# dab_mainboard.net
KiCad netlist of a schematic drawn in EAGLE
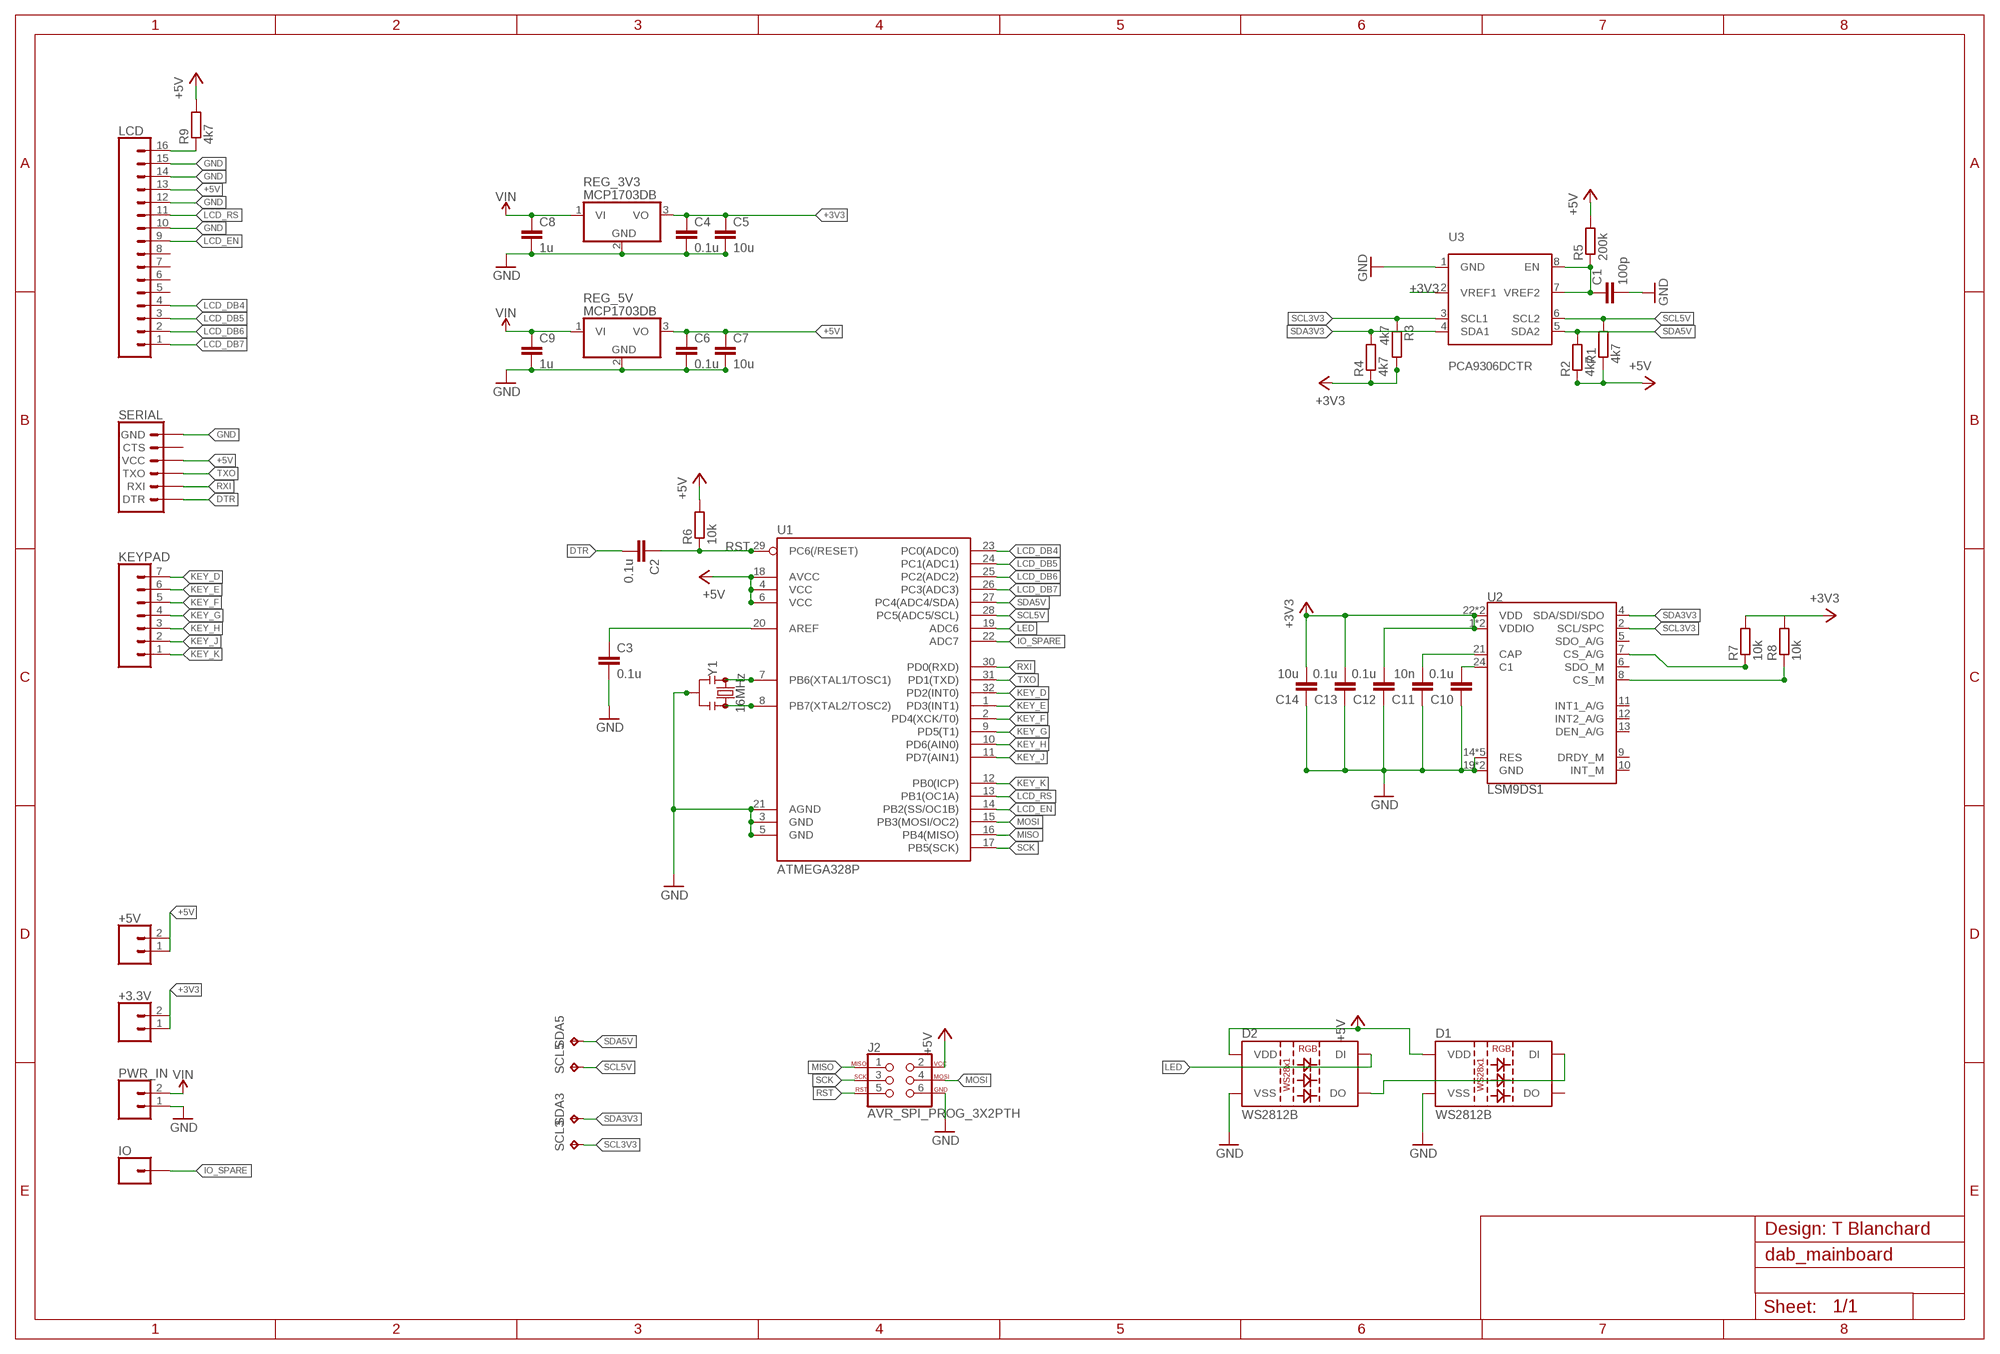
[diagram p0: schematic, sheet 1]

(export (version "E")
  (design (tool "Eeschema 10.0.6"))
  (components
    (comp (ref "+3.3V")
      (value "CONN_02")
      (footprint "eagle-import:1X02")
      (libsource (lib "eagle-import") (part "CONN_02"))
    )
    (comp (ref "+5V")
      (value "CONN_02")
      (footprint "eagle-import:1X02")
      (libsource (lib "eagle-import") (part "CONN_02"))
    )
    (comp (ref "C1")
      (value "100p")
      (footprint "eagle-import:C0603")
      (libsource (lib "eagle-import") (part "C-EUC0603"))
    )
    (comp (ref "C2")
      (value "0.1u")
      (footprint "eagle-import:C0603")
      (libsource (lib "eagle-import") (part "C-EUC0603"))
    )
    (comp (ref "C3")
      (value "0.1u")
      (footprint "eagle-import:C0603")
      (libsource (lib "eagle-import") (part "C-EUC0603"))
    )
    (comp (ref "C4")
      (value "0.1u")
      (footprint "eagle-import:C0603")
      (libsource (lib "eagle-import") (part "C-EUC0603"))
    )
    (comp (ref "C5")
      (value "10u")
      (footprint "eagle-import:C0603")
      (libsource (lib "eagle-import") (part "C-EUC0603"))
    )
    (comp (ref "C6")
      (value "0.1u")
      (footprint "eagle-import:C0603")
      (libsource (lib "eagle-import") (part "C-EUC0603"))
    )
    (comp (ref "C7")
      (value "10u")
      (footprint "eagle-import:C0603")
      (libsource (lib "eagle-import") (part "C-EUC0603"))
    )
    (comp (ref "C8")
      (value "1u")
      (footprint "eagle-import:C0603")
      (libsource (lib "eagle-import") (part "C-EUC0603"))
    )
    (comp (ref "C9")
      (value "1u")
      (footprint "eagle-import:C0603")
      (libsource (lib "eagle-import") (part "C-EUC0603"))
    )
    (comp (ref "C10")
      (value "0.1u")
      (footprint "eagle-import:C0603")
      (libsource (lib "eagle-import") (part "C-EUC0603"))
    )
    (comp (ref "C11")
      (value "10n")
      (footprint "eagle-import:C0603")
      (libsource (lib "eagle-import") (part "C-EUC0603"))
    )
    (comp (ref "C12")
      (value "0.1u")
      (footprint "eagle-import:C0603")
      (libsource (lib "eagle-import") (part "C-EUC0603"))
    )
    (comp (ref "C13")
      (value "0.1u")
      (footprint "eagle-import:C0603")
      (libsource (lib "eagle-import") (part "C-EUC0603"))
    )
    (comp (ref "C14")
      (value "10u")
      (footprint "eagle-import:C0603")
      (libsource (lib "eagle-import") (part "C-EUC0603"))
    )
    (comp (ref "D1")
      (value "WS2812B")
      (footprint "eagle-import:WS2812B")
      (libsource (lib "eagle-import") (part "WS2812B"))
    )
    (comp (ref "D2")
      (value "WS2812B")
      (footprint "eagle-import:WS2812B")
      (libsource (lib "eagle-import") (part "WS2812B"))
    )
    (comp (ref "IO")
      (value "CONN_01")
      (footprint "eagle-import:1X01")
      (libsource (lib "eagle-import") (part "CONN_01"))
    )
    (comp (ref "J2")
      (value "AVR_SPI_PROG_3X2PTH")
      (footprint "eagle-import:2X3")
      (libsource (lib "eagle-import") (part "AVR_SPI_PROG_3X2PTH"))
    )
    (comp (ref "KEYPAD")
      (value "CONN_07")
      (footprint "eagle-import:1X07")
      (libsource (lib "eagle-import") (part "CONN_07"))
    )
    (comp (ref "LCD")
      (value "CONN_16")
      (footprint "eagle-import:1X16")
      (libsource (lib "eagle-import") (part "CONN_16"))
    )
    (comp (ref "PWR_IN")
      (value "CONN_02")
      (footprint "eagle-import:1X02")
      (libsource (lib "eagle-import") (part "CONN_02"))
    )
    (comp (ref "R1")
      (value "4k7")
      (footprint "eagle-import:R0603")
      (libsource (lib "eagle-import") (part "R-EU_R0603"))
    )
    (comp (ref "R2")
      (value "4k7")
      (footprint "eagle-import:R0603")
      (libsource (lib "eagle-import") (part "R-EU_R0603"))
    )
    (comp (ref "R3")
      (value "4k7")
      (footprint "eagle-import:R0603")
      (libsource (lib "eagle-import") (part "R-EU_R0603"))
    )
    (comp (ref "R4")
      (value "4k7")
      (footprint "eagle-import:R0603")
      (libsource (lib "eagle-import") (part "R-EU_R0603"))
    )
    (comp (ref "R5")
      (value "200k")
      (footprint "eagle-import:R0603")
      (libsource (lib "eagle-import") (part "R-EU_R0603"))
    )
    (comp (ref "R6")
      (value "10k")
      (footprint "eagle-import:R0603")
      (libsource (lib "eagle-import") (part "R-EU_R0603"))
    )
    (comp (ref "R7")
      (value "10k")
      (footprint "eagle-import:R0603")
      (libsource (lib "eagle-import") (part "R-EU_R0603"))
    )
    (comp (ref "R8")
      (value "10k")
      (footprint "eagle-import:R0603")
      (libsource (lib "eagle-import") (part "R-EU_R0603"))
    )
    (comp (ref "R9")
      (value "4k7")
      (footprint "eagle-import:R0603")
      (libsource (lib "eagle-import") (part "R-EU_R0603"))
    )
    (comp (ref "REG_3V3")
      (value "MCP1703DB")
      (footprint "eagle-import:SOT223")
      (libsource (lib "eagle-import") (part "MCP1703DB"))
    )
    (comp (ref "REG_5V")
      (value "MCP1703DB")
      (footprint "eagle-import:SOT223")
      (libsource (lib "eagle-import") (part "MCP1703DB"))
    )
    (comp (ref "SCL3")
      (value "TPTP08R")
      (footprint "eagle-import:TP08R")
      (libsource (lib "eagle-import") (part "TPTP08R"))
    )
    (comp (ref "SCL5")
      (value "TPTP08R")
      (footprint "eagle-import:TP08R")
      (libsource (lib "eagle-import") (part "TPTP08R"))
    )
    (comp (ref "SDA3")
      (value "TPTP08R")
      (footprint "eagle-import:TP08R")
      (libsource (lib "eagle-import") (part "TPTP08R"))
    )
    (comp (ref "SDA5")
      (value "TPTP08R")
      (footprint "eagle-import:TP08R")
      (libsource (lib "eagle-import") (part "TPTP08R"))
    )
    (comp (ref "SERIAL")
      (value "6_PIN_SERIAL_TARGETSILK")
      (footprint "eagle-import:6_PIN_SERIAL_TARGET_SIDE_W_SILK")
      (libsource (lib "eagle-import") (part "6_PIN_SERIAL_TARGETSILK"))
    )
    (comp (ref "U1")
      (value "ATMEGA328P")
      (footprint "eagle-import:TQFP32-08")
      (libsource (lib "eagle-import") (part "ATMEGA328P_TQFP"))
    )
    (comp (ref "U2")
      (value "LSM9DS1")
      (footprint "eagle-import:LGA-24-3.5X3")
      (libsource (lib "eagle-import") (part "LSM9DS1"))
    )
    (comp (ref "U3")
      (value "PCA9306DCTR")
      (footprint "eagle-import:SM8")
      (libsource (lib "eagle-import") (part "PCA9306DCTR"))
    )
    (comp (ref "Y1")
      (value "16MHz")
      (footprint "eagle-import:RESONATOR-SMD-3.2X1.3")
      (libsource (lib "eagle-import") (part "RESONATOR-16MHZSMD_3.2X1.3"))
    )
  )
  (nets
    (net (code "1") (name "+3V3") (class "Default")
      (node (ref "+3.3V") (pin "1") (pinfunction "1_1") (pintype "passive"))
      (node (ref "+3.3V") (pin "2") (pinfunction "2_2") (pintype "passive"))
      (node (ref "C12") (pin "2") (pinfunction "2_2") (pintype "passive"))
      (node (ref "C13") (pin "2") (pinfunction "2_2") (pintype "passive"))
      (node (ref "C14") (pin "2") (pinfunction "2_2") (pintype "passive"))
      (node (ref "C4") (pin "1") (pinfunction "1_1") (pintype "passive"))
      (node (ref "C5") (pin "1") (pinfunction "1_1") (pintype "passive"))
      (node (ref "R3") (pin "2") (pinfunction "2_2") (pintype "passive"))
      (node (ref "R4") (pin "1") (pinfunction "1_1") (pintype "passive"))
      (node (ref "R7") (pin "2") (pinfunction "2_2") (pintype "passive"))
      (node (ref "R8") (pin "2") (pinfunction "2_2") (pintype "passive"))
      (node (ref "REG_3V3") (pin "3") (pinfunction "VO_3") (pintype "passive"))
      (node (ref "U2") (pin "1") (pinfunction "VDDIO_1") (pintype "bidirectional"))
      (node (ref "U2") (pin "22") (pinfunction "VDD_22") (pintype "bidirectional"))
      (node (ref "U2") (pin "23") (pinfunction "VDD_23") (pintype "bidirectional"))
      (node (ref "U2") (pin "3") (pinfunction "VDDIO_3") (pintype "bidirectional"))
      (node (ref "U3") (pin "2") (pinfunction "VREF1_2") (pintype "power_in"))
    )
    (net (code "2") (name "+5V") (class "Default")
      (node (ref "+5V") (pin "1") (pinfunction "1_1") (pintype "passive"))
      (node (ref "+5V") (pin "2") (pinfunction "2_2") (pintype "passive"))
      (node (ref "C6") (pin "1") (pinfunction "1_1") (pintype "passive"))
      (node (ref "C7") (pin "1") (pinfunction "1_1") (pintype "passive"))
      (node (ref "D1") (pin "1") (pinfunction "VDD_1") (pintype "bidirectional"))
      (node (ref "D2") (pin "1") (pinfunction "VDD_1") (pintype "bidirectional"))
      (node (ref "J2") (pin "2") (pinfunction "2_2") (pintype "passive"))
      (node (ref "LCD") (pin "13") (pinfunction "13_13") (pintype "passive"))
      (node (ref "R1") (pin "1") (pinfunction "1_1") (pintype "passive"))
      (node (ref "R2") (pin "1") (pinfunction "1_1") (pintype "passive"))
      (node (ref "R5") (pin "2") (pinfunction "2_2") (pintype "passive"))
      (node (ref "R6") (pin "2") (pinfunction "2_2") (pintype "passive"))
      (node (ref "R9") (pin "2") (pinfunction "2_2") (pintype "passive"))
      (node (ref "REG_5V") (pin "3") (pinfunction "VO_3") (pintype "passive"))
      (node (ref "SERIAL") (pin "P$4") (pinfunction "VCC_P$4") (pintype "passive"))
      (node (ref "U1") (pin "18") (pinfunction "AVCC_18") (pintype "bidirectional"))
      (node (ref "U1") (pin "4") (pinfunction "VCC_4") (pintype "bidirectional"))
      (node (ref "U1") (pin "6") (pinfunction "VCC_6") (pintype "bidirectional"))
    )
    (net (code "3") (name "DTR") (class "Default")
      (node (ref "C2") (pin "2") (pinfunction "2_2") (pintype "passive"))
      (node (ref "SERIAL") (pin "P$1") (pinfunction "DTR_P$1") (pintype "passive"))
    )
    (net (code "4") (name "GND") (class "Default")
      (node (ref "C1") (pin "2") (pinfunction "2_2") (pintype "passive"))
      (node (ref "C10") (pin "1") (pinfunction "1_1") (pintype "passive"))
      (node (ref "C11") (pin "1") (pinfunction "1_1") (pintype "passive"))
      (node (ref "C12") (pin "1") (pinfunction "1_1") (pintype "passive"))
      (node (ref "C13") (pin "1") (pinfunction "1_1") (pintype "passive"))
      (node (ref "C14") (pin "1") (pinfunction "1_1") (pintype "passive"))
      (node (ref "C3") (pin "2") (pinfunction "2_2") (pintype "passive"))
      (node (ref "C4") (pin "2") (pinfunction "2_2") (pintype "passive"))
      (node (ref "C5") (pin "2") (pinfunction "2_2") (pintype "passive"))
      (node (ref "C6") (pin "2") (pinfunction "2_2") (pintype "passive"))
      (node (ref "C7") (pin "2") (pinfunction "2_2") (pintype "passive"))
      (node (ref "C8") (pin "2") (pinfunction "2_2") (pintype "passive"))
      (node (ref "C9") (pin "2") (pinfunction "2_2") (pintype "passive"))
      (node (ref "D1") (pin "3") (pinfunction "VSS_3") (pintype "bidirectional"))
      (node (ref "D2") (pin "3") (pinfunction "VSS_3") (pintype "bidirectional"))
      (node (ref "J2") (pin "6") (pinfunction "6_6") (pintype "passive"))
      (node (ref "LCD") (pin "10") (pinfunction "10_10") (pintype "passive"))
      (node (ref "LCD") (pin "12") (pinfunction "12_12") (pintype "passive"))
      (node (ref "LCD") (pin "14") (pinfunction "14_14") (pintype "passive"))
      (node (ref "LCD") (pin "15") (pinfunction "15_15") (pintype "passive"))
      (node (ref "PWR_IN") (pin "1") (pinfunction "1_1") (pintype "passive"))
      (node (ref "REG_3V3") (pin "2") (pinfunction "GND_2") (pintype "passive"))
      (node (ref "REG_5V") (pin "2") (pinfunction "GND_2") (pintype "passive"))
      (node (ref "SERIAL") (pin "P$6") (pinfunction "GND_P$6") (pintype "passive"))
      (node (ref "U1") (pin "21") (pinfunction "AGND_21") (pintype "bidirectional"))
      (node (ref "U1") (pin "3") (pinfunction "GND_3") (pintype "bidirectional"))
      (node (ref "U1") (pin "5") (pinfunction "GND_5") (pintype "bidirectional"))
      (node (ref "U2") (pin "14") (pinfunction "RES_14") (pintype "bidirectional"))
      (node (ref "U2") (pin "15") (pinfunction "RES_15") (pintype "bidirectional"))
      (node (ref "U2") (pin "16") (pinfunction "RES_16") (pintype "bidirectional"))
      (node (ref "U2") (pin "17") (pinfunction "RES_17") (pintype "bidirectional"))
      (node (ref "U2") (pin "18") (pinfunction "RES_18") (pintype "bidirectional"))
      (node (ref "U2") (pin "19") (pinfunction "GND_19") (pintype "bidirectional"))
      (node (ref "U2") (pin "20") (pinfunction "GND_20") (pintype "bidirectional"))
      (node (ref "U3") (pin "1") (pinfunction "GND_1") (pintype "power_in"))
      (node (ref "Y1") (pin "2") (pinfunction "2_2") (pintype "passive"))
    )
    (net (code "5") (name "IO_SPARE") (class "Default")
      (node (ref "IO") (pin "1") (pinfunction "1_1") (pintype "passive"))
      (node (ref "U1") (pin "22") (pinfunction "ADC7_22") (pintype "bidirectional"))
    )
    (net (code "6") (name "KEY_D") (class "Default")
      (node (ref "KEYPAD") (pin "7") (pinfunction "7_7") (pintype "passive"))
      (node (ref "U1") (pin "32") (pinfunction "PD2(INT0)_32") (pintype "bidirectional"))
    )
    (net (code "7") (name "KEY_E") (class "Default")
      (node (ref "KEYPAD") (pin "6") (pinfunction "6_6") (pintype "passive"))
      (node (ref "U1") (pin "1") (pinfunction "PD3(INT1)_1") (pintype "bidirectional"))
    )
    (net (code "8") (name "KEY_F") (class "Default")
      (node (ref "KEYPAD") (pin "5") (pinfunction "5_5") (pintype "passive"))
      (node (ref "U1") (pin "2") (pinfunction "PD4(XCK/T0)_2") (pintype "bidirectional"))
    )
    (net (code "9") (name "KEY_G") (class "Default")
      (node (ref "KEYPAD") (pin "4") (pinfunction "4_4") (pintype "passive"))
      (node (ref "U1") (pin "9") (pinfunction "PD5(T1)_9") (pintype "bidirectional"))
    )
    (net (code "10") (name "KEY_H") (class "Default")
      (node (ref "KEYPAD") (pin "3") (pinfunction "3_3") (pintype "passive"))
      (node (ref "U1") (pin "10") (pinfunction "PD6(AIN0)_10") (pintype "bidirectional"))
    )
    (net (code "11") (name "KEY_J") (class "Default")
      (node (ref "KEYPAD") (pin "2") (pinfunction "2_2") (pintype "passive"))
      (node (ref "U1") (pin "11") (pinfunction "PD7(AIN1)_11") (pintype "bidirectional"))
    )
    (net (code "12") (name "KEY_K") (class "Default")
      (node (ref "KEYPAD") (pin "1") (pinfunction "1_1") (pintype "passive"))
      (node (ref "U1") (pin "12") (pinfunction "PB0(ICP)_12") (pintype "bidirectional"))
    )
    (net (code "13") (name "LCD_DB4") (class "Default")
      (node (ref "LCD") (pin "4") (pinfunction "4_4") (pintype "passive"))
      (node (ref "U1") (pin "23") (pinfunction "PC0(ADC0)_23") (pintype "bidirectional"))
    )
    (net (code "14") (name "LCD_DB5") (class "Default")
      (node (ref "LCD") (pin "3") (pinfunction "3_3") (pintype "passive"))
      (node (ref "U1") (pin "24") (pinfunction "PC1(ADC1)_24") (pintype "bidirectional"))
    )
    (net (code "15") (name "LCD_DB6") (class "Default")
      (node (ref "LCD") (pin "2") (pinfunction "2_2") (pintype "passive"))
      (node (ref "U1") (pin "25") (pinfunction "PC2(ADC2)_25") (pintype "bidirectional"))
    )
    (net (code "16") (name "LCD_DB7") (class "Default")
      (node (ref "LCD") (pin "1") (pinfunction "1_1") (pintype "passive"))
      (node (ref "U1") (pin "26") (pinfunction "PC3(ADC3)_26") (pintype "bidirectional"))
    )
    (net (code "17") (name "LCD_EN") (class "Default")
      (node (ref "LCD") (pin "9") (pinfunction "9_9") (pintype "passive"))
      (node (ref "U1") (pin "14") (pinfunction "PB2(SS/OC1B)_14") (pintype "bidirectional"))
    )
    (net (code "18") (name "LCD_RS") (class "Default")
      (node (ref "LCD") (pin "11") (pinfunction "11_11") (pintype "passive"))
      (node (ref "U1") (pin "13") (pinfunction "PB1(OC1A)_13") (pintype "bidirectional"))
    )
    (net (code "19") (name "LED") (class "Default")
      (node (ref "D2") (pin "4") (pinfunction "DI_4") (pintype "bidirectional"))
      (node (ref "U1") (pin "19") (pinfunction "ADC6_19") (pintype "bidirectional"))
    )
    (net (code "20") (name "MISO") (class "Default")
      (node (ref "J2") (pin "1") (pinfunction "1_1") (pintype "passive"))
      (node (ref "U1") (pin "16") (pinfunction "PB4(MISO)_16") (pintype "bidirectional"))
    )
    (net (code "21") (name "MOSI") (class "Default")
      (node (ref "J2") (pin "4") (pinfunction "4_4") (pintype "passive"))
      (node (ref "U1") (pin "15") (pinfunction "PB3(MOSI/OC2)_15") (pintype "bidirectional"))
    )
    (net (code "22") (name "Net-(D1-DI)") (class "Default")
      (node (ref "D1") (pin "4") (pinfunction "DI_4") (pintype "bidirectional"))
      (node (ref "D2") (pin "2") (pinfunction "DO_2") (pintype "bidirectional"))
    )
    (net (code "23") (name "Net-(LCD-Pad16)") (class "Default")
      (node (ref "LCD") (pin "16") (pinfunction "16_16") (pintype "passive"))
      (node (ref "R9") (pin "1") (pinfunction "1_1") (pintype "passive"))
    )
    (net (code "24") (name "Net-(U1-AREF)") (class "Default")
      (node (ref "C3") (pin "1") (pinfunction "1_1") (pintype "passive"))
      (node (ref "U1") (pin "20") (pinfunction "AREF_20") (pintype "bidirectional"))
    )
    (net (code "25") (name "Net-(U1-PB6(XTAL1{slash}TOSC1))") (class "Default")
      (node (ref "U1") (pin "7") (pinfunction "PB6(XTAL1/TOSC1)_7") (pintype "bidirectional"))
      (node (ref "Y1") (pin "1") (pinfunction "1_1") (pintype "passive"))
    )
    (net (code "26") (name "Net-(U1-PB7(XTAL2{slash}TOSC2))") (class "Default")
      (node (ref "U1") (pin "8") (pinfunction "PB7(XTAL2/TOSC2)_8") (pintype "bidirectional"))
      (node (ref "Y1") (pin "3") (pinfunction "3_3") (pintype "passive"))
    )
    (net (code "27") (name "Net-(U2-C1)") (class "Default")
      (node (ref "C10") (pin "2") (pinfunction "2_2") (pintype "passive"))
      (node (ref "U2") (pin "24") (pinfunction "C1_24") (pintype "bidirectional"))
    )
    (net (code "28") (name "Net-(U2-CAP)") (class "Default")
      (node (ref "C11") (pin "2") (pinfunction "2_2") (pintype "passive"))
      (node (ref "U2") (pin "21") (pinfunction "CAP_21") (pintype "bidirectional"))
    )
    (net (code "29") (name "Net-(U2-CS_A{slash}G)") (class "Default")
      (node (ref "R7") (pin "1") (pinfunction "1_1") (pintype "passive"))
      (node (ref "U2") (pin "7") (pinfunction "CS_A/G_7") (pintype "bidirectional"))
    )
    (net (code "30") (name "Net-(U2-CS_M)") (class "Default")
      (node (ref "R8") (pin "1") (pinfunction "1_1") (pintype "passive"))
      (node (ref "U2") (pin "8") (pinfunction "CS_M_8") (pintype "bidirectional"))
    )
    (net (code "31") (name "Net-(U3-EN)") (class "Default")
      (node (ref "C1") (pin "1") (pinfunction "1_1") (pintype "passive"))
      (node (ref "R5") (pin "1") (pinfunction "1_1") (pintype "passive"))
      (node (ref "U3") (pin "7") (pinfunction "VREF2_7") (pintype "power_in"))
      (node (ref "U3") (pin "8") (pinfunction "EN_8") (pintype "input"))
    )
    (net (code "32") (name "RST") (class "Default")
      (node (ref "C2") (pin "1") (pinfunction "1_1") (pintype "passive"))
      (node (ref "J2") (pin "5") (pinfunction "5_5") (pintype "passive"))
      (node (ref "R6") (pin "1") (pinfunction "1_1") (pintype "passive"))
      (node (ref "U1") (pin "29") (pinfunction "PC6(/RESET)_29") (pintype "bidirectional"))
    )
    (net (code "33") (name "RXI") (class "Default")
      (node (ref "SERIAL") (pin "P$3") (pinfunction "RXI_P$3") (pintype "passive"))
      (node (ref "U1") (pin "30") (pinfunction "PD0(RXD)_30") (pintype "bidirectional"))
    )
    (net (code "34") (name "SCK") (class "Default")
      (node (ref "J2") (pin "3") (pinfunction "3_3") (pintype "passive"))
      (node (ref "U1") (pin "17") (pinfunction "PB5(SCK)_17") (pintype "bidirectional"))
    )
    (net (code "35") (name "SCL3V3") (class "Default")
      (node (ref "R3") (pin "1") (pinfunction "1_1") (pintype "passive"))
      (node (ref "SCL3") (pin "TP") (pinfunction "TP_TP") (pintype "input"))
      (node (ref "U2") (pin "2") (pinfunction "SCL/SPC_2") (pintype "bidirectional"))
      (node (ref "U3") (pin "3") (pinfunction "SCL1_3") (pintype "bidirectional"))
    )
    (net (code "36") (name "SCL5V") (class "Default")
      (node (ref "R1") (pin "2") (pinfunction "2_2") (pintype "passive"))
      (node (ref "SCL5") (pin "TP") (pinfunction "TP_TP") (pintype "input"))
      (node (ref "U1") (pin "28") (pinfunction "PC5(ADC5/SCL)_28") (pintype "bidirectional"))
      (node (ref "U3") (pin "6") (pinfunction "SCL2_6") (pintype "bidirectional"))
    )
    (net (code "37") (name "SDA3V3") (class "Default")
      (node (ref "R4") (pin "2") (pinfunction "2_2") (pintype "passive"))
      (node (ref "SDA3") (pin "TP") (pinfunction "TP_TP") (pintype "input"))
      (node (ref "U2") (pin "4") (pinfunction "SDA/SDI/SDO_4") (pintype "bidirectional"))
      (node (ref "U3") (pin "4") (pinfunction "SDA1_4") (pintype "bidirectional"))
    )
    (net (code "38") (name "SDA5V") (class "Default")
      (node (ref "R2") (pin "2") (pinfunction "2_2") (pintype "passive"))
      (node (ref "SDA5") (pin "TP") (pinfunction "TP_TP") (pintype "input"))
      (node (ref "U1") (pin "27") (pinfunction "PC4(ADC4/SDA)_27") (pintype "bidirectional"))
      (node (ref "U3") (pin "5") (pinfunction "SDA2_5") (pintype "bidirectional"))
    )
    (net (code "39") (name "TXO") (class "Default")
      (node (ref "SERIAL") (pin "P$2") (pinfunction "TXO_P$2") (pintype "passive"))
      (node (ref "U1") (pin "31") (pinfunction "PD1(TXD)_31") (pintype "bidirectional"))
    )
    (net (code "40") (name "VIN") (class "Default")
      (node (ref "C8") (pin "1") (pinfunction "1_1") (pintype "passive"))
      (node (ref "C9") (pin "1") (pinfunction "1_1") (pintype "passive"))
      (node (ref "PWR_IN") (pin "2") (pinfunction "2_2") (pintype "passive"))
      (node (ref "REG_3V3") (pin "1") (pinfunction "VI_1") (pintype "input"))
      (node (ref "REG_5V") (pin "1") (pinfunction "VI_1") (pintype "input"))
    )
    (net (code "41") (name "unconnected-(D1-DO-Pad2)") (class "Default")
      (node (ref "D1") (pin "2") (pinfunction "DO_2") (pintype "bidirectional"))
    )
    (net (code "42") (name "unconnected-(LCD-Pad5)") (class "Default")
      (node (ref "LCD") (pin "5") (pinfunction "5_5") (pintype "passive"))
    )
    (net (code "43") (name "unconnected-(LCD-Pad6)") (class "Default")
      (node (ref "LCD") (pin "6") (pinfunction "6_6") (pintype "passive"))
    )
    (net (code "44") (name "unconnected-(LCD-Pad7)") (class "Default")
      (node (ref "LCD") (pin "7") (pinfunction "7_7") (pintype "passive"))
    )
    (net (code "45") (name "unconnected-(LCD-Pad8)") (class "Default")
      (node (ref "LCD") (pin "8") (pinfunction "8_8") (pintype "passive"))
    )
    (net (code "46") (name "unconnected-(SERIAL-CTS-PadP$5)") (class "Default")
      (node (ref "SERIAL") (pin "P$5") (pinfunction "CTS_P$5") (pintype "passive"))
    )
    (net (code "47") (name "unconnected-(U2-DEN_A{slash}G-Pad13)") (class "Default")
      (node (ref "U2") (pin "13") (pinfunction "DEN_A/G_13") (pintype "bidirectional"))
    )
    (net (code "48") (name "unconnected-(U2-DRDY_M-Pad9)") (class "Default")
      (node (ref "U2") (pin "9") (pinfunction "DRDY_M_9") (pintype "bidirectional"))
    )
    (net (code "49") (name "unconnected-(U2-INT1_A{slash}G-Pad11)") (class "Default")
      (node (ref "U2") (pin "11") (pinfunction "INT1_A/G_11") (pintype "bidirectional"))
    )
    (net (code "50") (name "unconnected-(U2-INT2_A{slash}G-Pad12)") (class "Default")
      (node (ref "U2") (pin "12") (pinfunction "INT2_A/G_12") (pintype "bidirectional"))
    )
    (net (code "51") (name "unconnected-(U2-INT_M-Pad10)") (class "Default")
      (node (ref "U2") (pin "10") (pinfunction "INT_M_10") (pintype "bidirectional"))
    )
    (net (code "52") (name "unconnected-(U2-SDO_A{slash}G-Pad5)") (class "Default")
      (node (ref "U2") (pin "5") (pinfunction "SDO_A/G_5") (pintype "bidirectional"))
    )
    (net (code "53") (name "unconnected-(U2-SDO_M-Pad6)") (class "Default")
      (node (ref "U2") (pin "6") (pinfunction "SDO_M_6") (pintype "bidirectional"))
    )
  )
)
